# TLM_002_MCP3021.net
KiCad netlist of a schematic drawn in Altium Designer
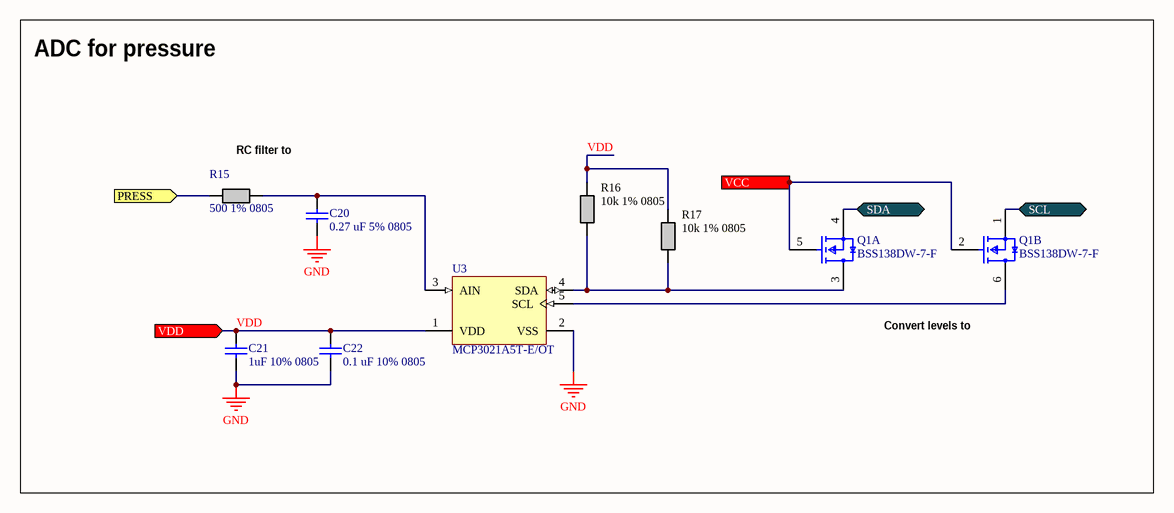
[diagram p0: TLM_002_MCP3021.SchDoc]

(export (version "E")
  (design (tool "Eeschema 10.0.6"))
  (components
    (comp (ref "C20")
      (value "0.27 uF 5% 0805")
      (footprint "CAPC2013X145X50ML20T20")
      (fields (field (name "PART NUMBER") "VJ0805Y274JXXTW1BC") (field (name "MANUFACTURER") "Vitramon"))
      (libsource (lib "Altium Content Vault") (part "CAP"))
    )
    (comp (ref "C21")
      (value "1uF 10% 0805")
      (footprint "CAPC2013X145X50NL20T20")
      (fields (field (name "PART NUMBER") "VJ0805Y105KXQRW1BC") (field (name "MANUFACTURER") "Vitramon"))
      (libsource (lib "Altium Content Vault") (part "CAP"))
    )
    (comp (ref "C22")
      (value "0.1 uF 10% 0805")
      (footprint "CAPC2013X140X50ML20T25")
      (fields
        (field (name "PART NUMBER") "0805DD104KAT2A")
        (field (name "MANUFACTURER") "AVX Interconnect / Elco")
      )
      (libsource (lib "Altium Content Vault") (part "CAP"))
    )
    (comp (ref "Q1")
      (value "BSS138DW-7-F")
      (footprint "FP-SOT363-IPC_B")
      (description "MOSFET 2N-CH 50V 0.2A SC70-6")
      (libsource (lib "Altium Content Vault") (part "297539c3904897ba936602102abf918"))
    )
    (comp (ref "R15")
      (value "500 1% 0805")
      (footprint "RES_0805")
      (description "Resistor 500Ohm 1% SMD 0805 Generic")
      (fields (field (name "TOLERANCE") "1%"))
      (libsource (lib "Generic-Schematic-Library") (part "Resistor_500"))
    )
    (comp (ref "R16")
      (value "10k 1% 0805")
      (footprint "RES_0805")
      (description "Resistor 10kOhm 1% SMD 0805 Generic")
      (fields (field (name "TOLERANCE") "1%"))
      (libsource (lib "Generic-Schematic-Library") (part "Resistor_10k"))
    )
    (comp (ref "R17")
      (value "10k 1% 0805")
      (footprint "RES_0805")
      (description "Resistor 10kOhm 1% SMD 0805 Generic")
      (fields (field (name "TOLERANCE") "1%"))
      (libsource (lib "Generic-Schematic-Library") (part "Resistor_10k"))
    )
    (comp (ref "U3")
      (value "MCP3021A5T-E/OT")
      (footprint "SOT-23-OT5_L")
      (libsource (lib "Altium Content Vault") (part "CON-ADC-MCP3021-5"))
    )
  )
  (nets
    (net (code "1") (name "/PRESS") (class "Default")
      (node (ref "R15") (pin "1") (pinfunction "1_1") (pintype "passive"))
    )
    (net (code "2") (name "/SCL") (class "Default")
      (node (ref "Q1") (pin "1") (pinfunction "S2_1") (pintype "passive"))
    )
    (net (code "3") (name "/SDA") (class "Default")
      (node (ref "Q1") (pin "4") (pinfunction "S1_4") (pintype "passive"))
    )
    (net (code "4") (name "/VCC") (class "Default")
      (node (ref "Q1") (pin "2") (pinfunction "G2_2") (pintype "passive"))
      (node (ref "Q1") (pin "5") (pinfunction "G1_5") (pintype "passive"))
    )
    (net (code "5") (name "/VDD") (class "Default")
      (node (ref "C21") (pin "2") (pinfunction "2_2") (pintype "passive"))
      (node (ref "C22") (pin "2") (pinfunction "2_2") (pintype "passive"))
      (node (ref "R16") (pin "1") (pinfunction "1_1") (pintype "passive"))
      (node (ref "R17") (pin "1") (pinfunction "1_1") (pintype "passive"))
      (node (ref "U3") (pin "1") (pinfunction "VDD_1") (pintype "passive"))
    )
    (net (code "6") (name "GND") (class "Default")
      (node (ref "C20") (pin "1") (pinfunction "1_1") (pintype "passive"))
      (node (ref "C21") (pin "1") (pinfunction "1_1") (pintype "passive"))
      (node (ref "C22") (pin "1") (pinfunction "1_1") (pintype "passive"))
      (node (ref "U3") (pin "2") (pinfunction "VSS_2") (pintype "power_in"))
    )
    (net (code "7") (name "Net-(Q1A-D1)") (class "Default")
      (node (ref "Q1") (pin "3") (pinfunction "D1_3") (pintype "passive"))
      (node (ref "R16") (pin "2") (pinfunction "2_2") (pintype "passive"))
      (node (ref "R17") (pin "2") (pinfunction "2_2") (pintype "passive"))
      (node (ref "U3") (pin "4") (pinfunction "SDA_4") (pintype "bidirectional"))
    )
    (net (code "8") (name "Net-(Q1B-D2)") (class "Default")
      (node (ref "Q1") (pin "6") (pinfunction "D2_6") (pintype "passive"))
      (node (ref "U3") (pin "5") (pinfunction "SCL_5") (pintype "input"))
    )
    (net (code "9") (name "Net-(U3-AIN)") (class "Default")
      (node (ref "C20") (pin "2") (pinfunction "2_2") (pintype "passive"))
      (node (ref "R15") (pin "2") (pinfunction "2_2") (pintype "passive"))
      (node (ref "U3") (pin "3") (pinfunction "AIN_3") (pintype "input"))
    )
  )
)
